# design.net
KiCad netlist of a schematic drawn in Altium Designer
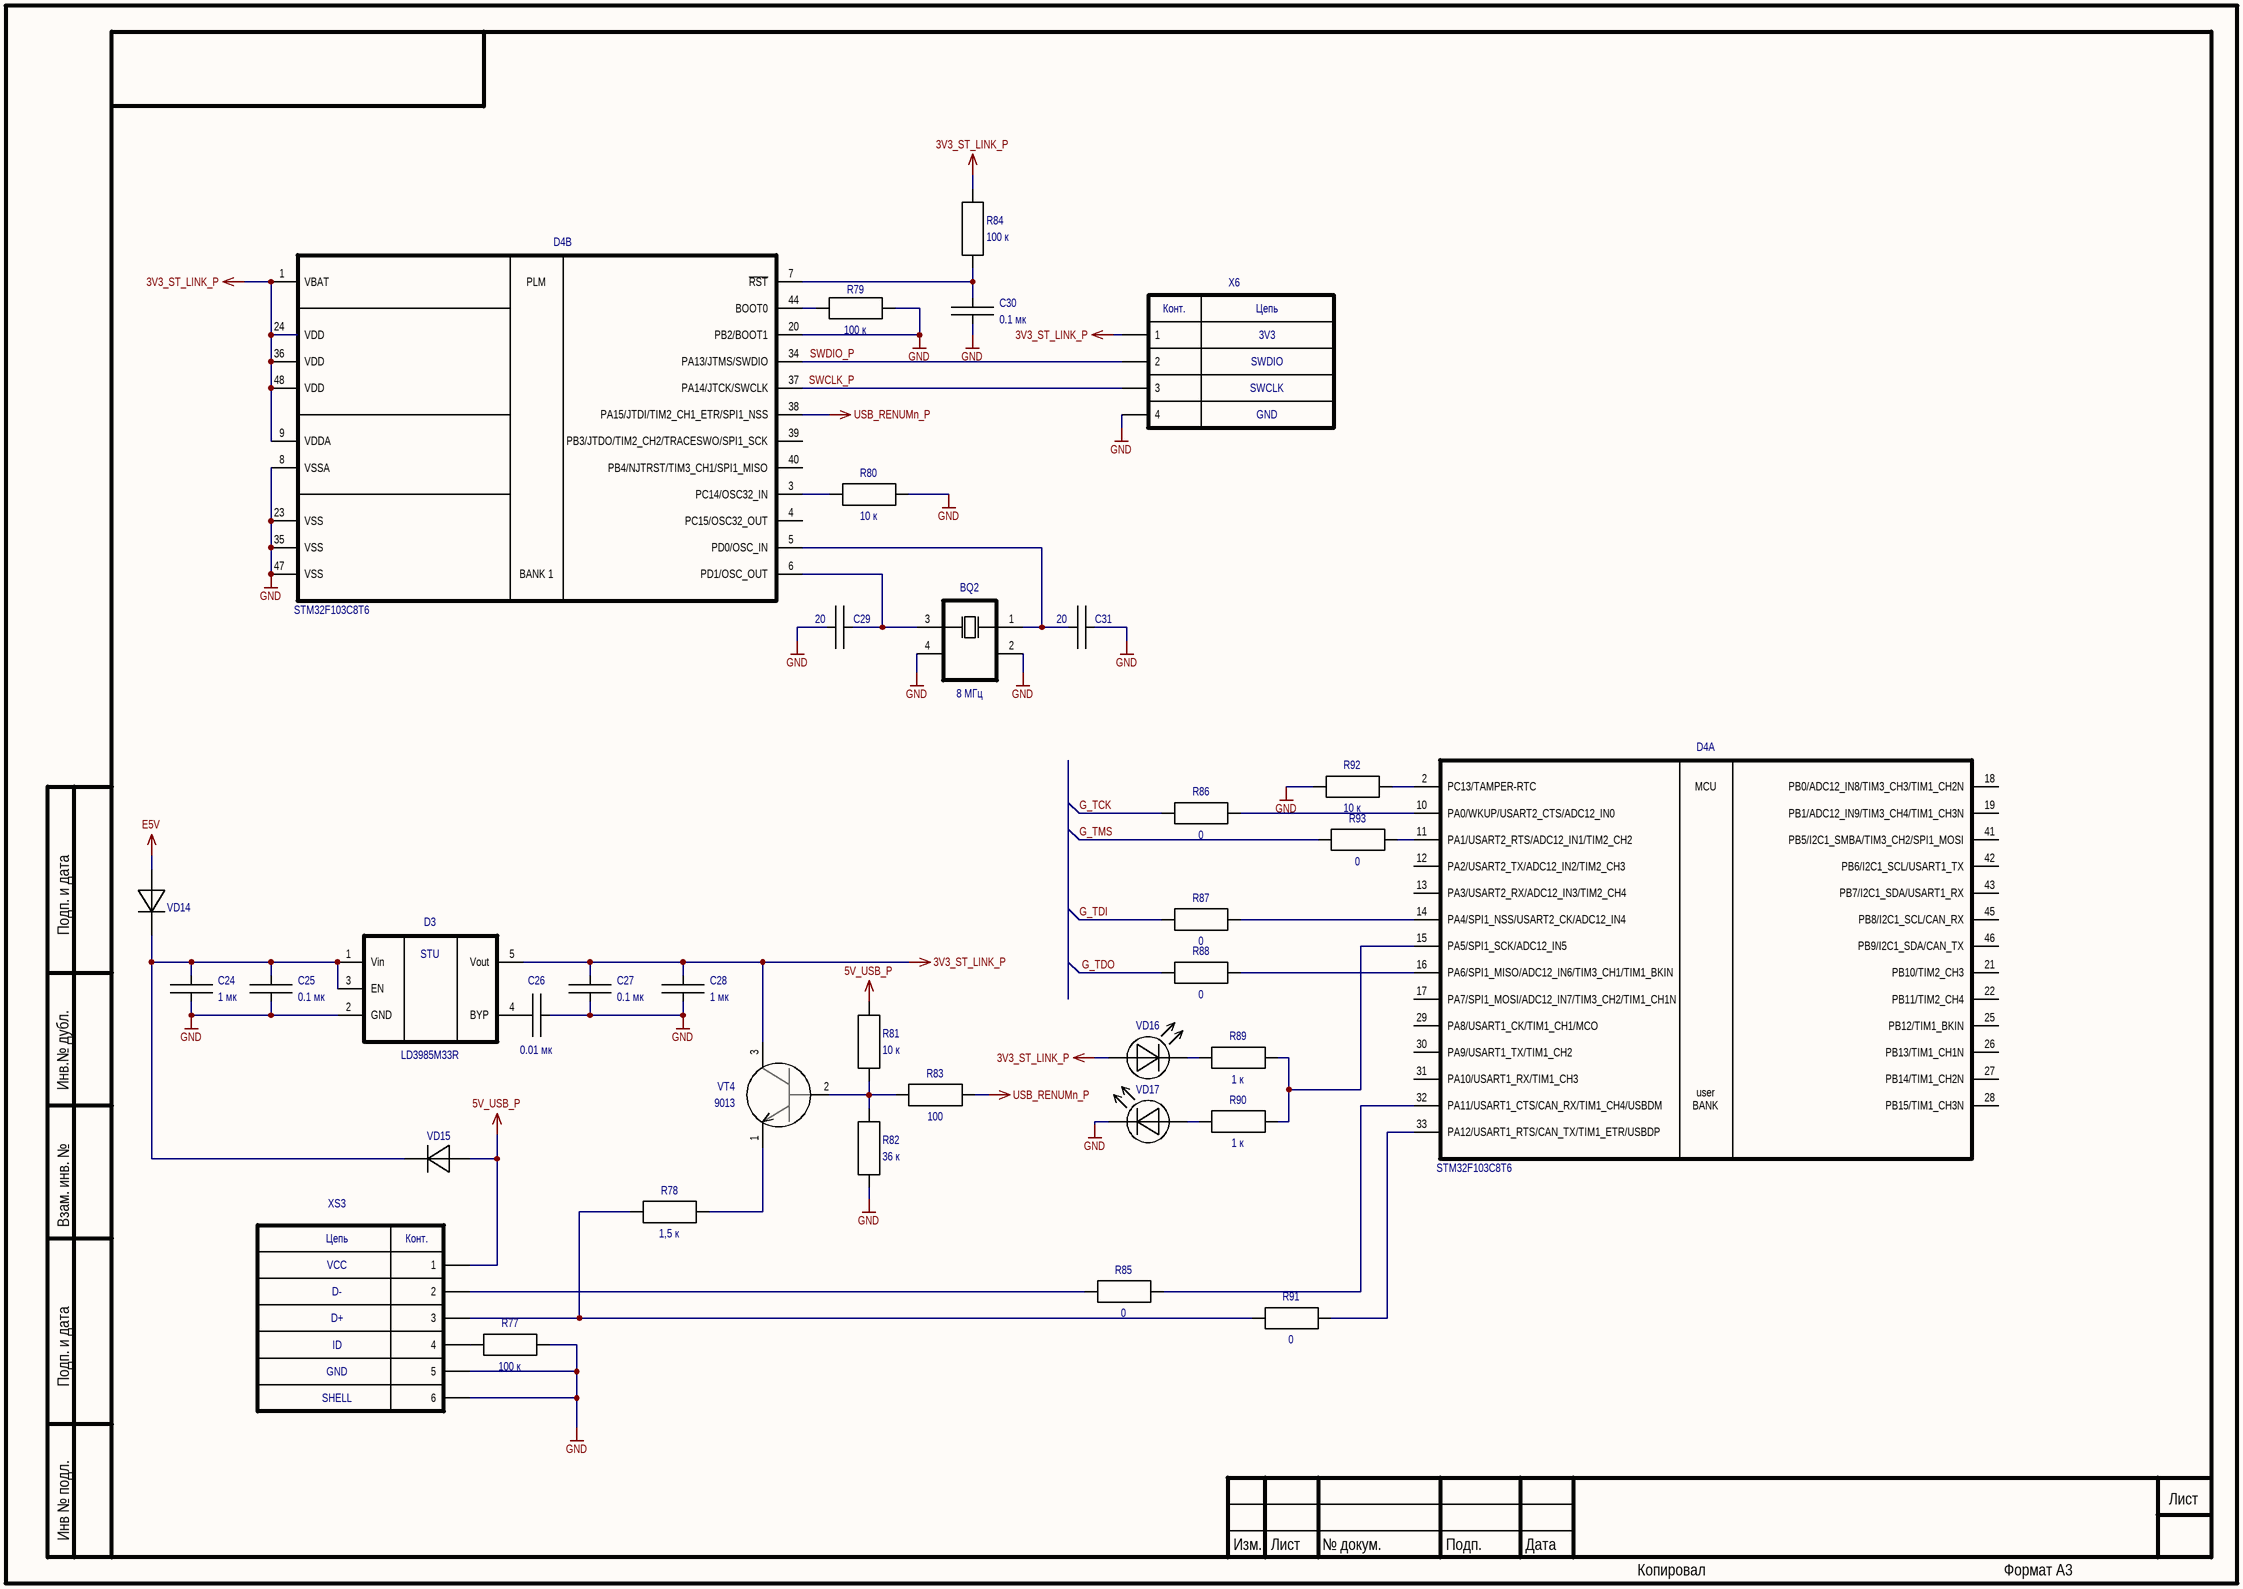
[diagram p0: программатор_ПЛИС.SchDoc]

(export (version "E")
  (design (tool "Eeschema 10.0.6"))
  (components
    (comp (ref "BQ2")
      (value "8 МГц")
      (footprint "SMD3225_4P20MHZ20PF10PPM")
      (fields (field (name "PARTNUMBER") "MQ-12.000-18") (field (name "Comment") "кварцевый резонатор_1"))
      (libsource (lib "Lisaveta_SCH") (part "кварцевый резонатор_1"))
    )
    (comp (ref "C24")
      (value "1 мк")
      (fields (field (name "Comment") "1 мкФ ±* * * *, *"))
      (libsource (lib "Lisaveta") (part "C"))
    )
    (comp (ref "C25")
      (value "0.1 мк")
      (fields (field (name "Comment") "0.1 мкФ ±* * * *, *"))
      (libsource (lib "Lisaveta") (part "C"))
    )
    (comp (ref "C26")
      (value "0.01 мк")
      (footprint "K10-79_1.6_0.8(0603)")
      (fields (field (name "Comment") "0.01 мкФ ±* * * *, *"))
      (libsource (lib "Lisaveta") (part "C"))
    )
    (comp (ref "C27")
      (value "0.1 мк")
      (fields (field (name "Comment") "0.1 мкФ ±* * * *, *"))
      (libsource (lib "Lisaveta") (part "C"))
    )
    (comp (ref "C28")
      (value "1 мк")
      (fields (field (name "Comment") "1 мкФ ±* * * *, *"))
      (libsource (lib "Lisaveta") (part "C"))
    )
    (comp (ref "C29")
      (value "20")
      (fields (field (name "Comment") "20Ф ±* * * *, *"))
      (libsource (lib "Lisaveta") (part "C"))
    )
    (comp (ref "C30")
      (value "0.1 мк")
      (fields (field (name "Comment") "0.1 мкФ ±* * * *, *"))
      (libsource (lib "Lisaveta") (part "C"))
    )
    (comp (ref "C31")
      (value "20")
      (fields (field (name "Comment") "20Ф ±* * * *, *"))
      (libsource (lib "Lisaveta") (part "C"))
    )
    (comp (ref "D3")
      (value "LD3985M33R")
      (footprint "SOT-23-5")
      (fields
        (field (name "PARTNUMBER") "LT1761ES5-2.5")
        (field (name "Comment") "LT1761ES5-2.5 (TSOT-23) Linear Technology")
      )
      (libsource (lib "Lisaveta") (part "LD3985M33R"))
    )
    (comp (ref "D4")
      (value "STM32F103C8T6")
      (footprint "LQFP48")
      (fields (field (name "Comment") " (LQFP-48) Xilinx"))
      (libsource (lib "Lisaveta") (part "stm32f103c8t6"))
    )
    (comp (ref "R77")
      (value "100 к")
      (fields (field (name "Comment") "100 кОм ±* *, *"))
      (libsource (lib "Lisaveta") (part "R"))
    )
    (comp (ref "R78")
      (value "1,5 к")
      (fields (field (name "Comment") "1,5 кОм ±* *, *"))
      (libsource (lib "Lisaveta") (part "R"))
    )
    (comp (ref "R79")
      (value "100 к")
      (fields (field (name "Comment") "100 кОм ±* *, *"))
      (libsource (lib "Lisaveta") (part "R"))
    )
    (comp (ref "R80")
      (value "10 к")
      (fields (field (name "Comment") "10 кОм ±* *, *"))
      (libsource (lib "Lisaveta") (part "R"))
    )
    (comp (ref "R81")
      (value "10 к")
      (fields (field (name "Comment") "10 кОм ±* *, *"))
      (libsource (lib "Lisaveta") (part "R_1"))
    )
    (comp (ref "R82")
      (value "36 к")
      (fields (field (name "Comment") "36 кОм ±* *, *"))
      (libsource (lib "Lisaveta") (part "R_1"))
    )
    (comp (ref "R83")
      (value "100")
      (fields (field (name "Comment") "100Ом ±* *, *"))
      (libsource (lib "Lisaveta") (part "R"))
    )
    (comp (ref "R84")
      (value "100 к")
      (footprint "RES 0603")
      (fields (field (name "Comment") "100 кОм ±* *, *"))
      (libsource (lib "Lisaveta") (part "R_1"))
    )
    (comp (ref "R85")
      (value "0")
      (fields (field (name "Comment") "0Ом ±* *, *"))
      (libsource (lib "Lisaveta") (part "R"))
    )
    (comp (ref "R86")
      (value "0")
      (fields (field (name "Comment") "0Ом ±* *, *"))
      (libsource (lib "Lisaveta") (part "R"))
    )
    (comp (ref "R87")
      (value "0")
      (fields (field (name "Comment") "0Ом ±* *, *"))
      (libsource (lib "Lisaveta") (part "R"))
    )
    (comp (ref "R88")
      (value "0")
      (fields (field (name "Comment") "0Ом ±* *, *"))
      (libsource (lib "Lisaveta") (part "R"))
    )
    (comp (ref "R89")
      (value "1 к")
      (fields (field (name "Comment") "1 кОм ±* *, *"))
      (libsource (lib "Lisaveta") (part "R"))
    )
    (comp (ref "R90")
      (value "1 к")
      (fields (field (name "Comment") "1 кОм ±* *, *"))
      (libsource (lib "Lisaveta") (part "R"))
    )
    (comp (ref "R91")
      (value "0")
      (fields (field (name "Comment") "0Ом ±* *, *"))
      (libsource (lib "") (part "R_1"))
    )
    (comp (ref "R92")
      (value "10 к")
      (fields (field (name "Comment") "10 кОм ±* *, *"))
      (libsource (lib "Lisaveta") (part "R"))
    )
    (comp (ref "R93")
      (value "0")
      (fields (field (name "Comment") "0Ом ±* *, *"))
      (libsource (lib "Lisaveta") (part "R"))
    )
    (comp (ref "VD14") (value "BAS316") (footprint "SOD323") (libsource (lib "Lisaveta") (part "BAS316")))
    (comp (ref "VD15") (value "BAS316") (footprint "SOD-323") (libsource (lib "Lisaveta") (part "BAS316")))
    (comp (ref "VD16")
      (value "Светодиод")
      (footprint "LED 0603")
      (libsource (lib "Lisaveta") (part "Светодиод"))
    )
    (comp (ref "VD17")
      (value "Светодиод")
      (footprint "LED 0603")
      (libsource (lib "Lisaveta") (part "Светодиод"))
    )
    (comp (ref "VT4")
      (value "9013")
      (footprint "SOT23(KT-46)")
      (fields (field (name "PARTNUMBER") "BC847C") (field (name "Comment") "BC847C (SOT-23) NXP"))
      (libsource (lib "Lisaveta") (part "T!9013"))
    )
    (comp (ref "X6")
      (value "KONT_POLE_4")
      (fields
        (field (name "1") "3V3")
        (field (name "2") "SWDIO")
        (field (name "3") "SWCLK")
        (field (name "4") "GND")
      )
      (libsource (lib "Lisaveta") (part "KONT_POLE_4"))
    )
    (comp (ref "XS3")
      (value "KONT_POLE_USB_DBG")
      (footprint "micro_USB")
      (fields
        (field (name "1") "VCC")
        (field (name "3") "D+")
        (field (name "2") "D-")
        (field (name "4") "ID")
        (field (name "6") "SHELL")
        (field (name "5") "GND")
      )
      (libsource (lib "Lisaveta") (part "KONT_POLE_USB_DBG"))
    )
  )
  (nets
    (net (code "1") (name "/G_TCK") (class "Default")
      (node (ref "R86") (pin "1") (pinfunction "1_1") (pintype "passive"))
    )
    (net (code "2") (name "/G_TDI") (class "Default")
      (node (ref "R87") (pin "1") (pinfunction "1_1") (pintype "passive"))
    )
    (net (code "3") (name "/G_TDO") (class "Default")
      (node (ref "R88") (pin "1") (pinfunction "1_1") (pintype "passive"))
    )
    (net (code "4") (name "/G_TMS") (class "Default")
      (node (ref "R93") (pin "1") (pinfunction "1_1") (pintype "passive"))
    )
    (net (code "5") (name "/SWCLK_P") (class "Default")
      (node (ref "D4") (pin "37") (pinfunction "PA14/JTCK/SWCLK_37") (pintype "passive"))
      (node (ref "X6") (pin "3") (pinfunction "3_3") (pintype "passive"))
    )
    (net (code "6") (name "/SWDIO_P") (class "Default")
      (node (ref "D4") (pin "34") (pinfunction "PA13/JTMS/SWDIO_34") (pintype "passive"))
      (node (ref "X6") (pin "2") (pinfunction "2_2") (pintype "passive"))
    )
    (net (code "7") (name "3V3_ST_LINK_P") (class "Default")
      (node (ref "C27") (pin "2") (pinfunction "2_2") (pintype "passive"))
      (node (ref "C28") (pin "2") (pinfunction "2_2") (pintype "passive"))
      (node (ref "D3") (pin "5") (pinfunction "Vout_5") (pintype "passive"))
      (node (ref "D4") (pin "1") (pinfunction "VBAT_1") (pintype "passive"))
      (node (ref "D4") (pin "24") (pinfunction "VDD_24") (pintype "passive"))
      (node (ref "D4") (pin "36") (pinfunction "VDD_36") (pintype "passive"))
      (node (ref "D4") (pin "48") (pinfunction "VDD_48") (pintype "passive"))
      (node (ref "D4") (pin "9") (pinfunction "VDDA_9") (pintype "passive"))
      (node (ref "R84") (pin "1") (pinfunction "1_1") (pintype "passive"))
      (node (ref "VD16") (pin "1") (pinfunction "A_1") (pintype "passive"))
      (node (ref "VT4") (pin "3") (pinfunction "3_3") (pintype "passive"))
      (node (ref "X6") (pin "1") (pinfunction "1_1") (pintype "passive"))
    )
    (net (code "8") (name "5V_USB_P") (class "Default")
      (node (ref "R81") (pin "1") (pinfunction "1_1") (pintype "passive"))
      (node (ref "VD15") (pin "1") (pinfunction "1_1") (pintype "passive"))
      (node (ref "XS3") (pin "1") (pinfunction "1_1") (pintype "passive"))
    )
    (net (code "9") (name "E5V") (class "Default")
      (node (ref "VD14") (pin "1") (pinfunction "1_1") (pintype "passive"))
    )
    (net (code "10") (name "GND") (class "Default")
      (node (ref "BQ2") (pin "2") (pinfunction "GND_2") (pintype "passive"))
      (node (ref "BQ2") (pin "4") (pinfunction "GND_4") (pintype "passive"))
      (node (ref "C24") (pin "1") (pinfunction "1_1") (pintype "passive"))
      (node (ref "C25") (pin "1") (pinfunction "1_1") (pintype "passive"))
      (node (ref "C26") (pin "1") (pinfunction "1_1") (pintype "passive"))
      (node (ref "C27") (pin "1") (pinfunction "1_1") (pintype "passive"))
      (node (ref "C28") (pin "1") (pinfunction "1_1") (pintype "passive"))
      (node (ref "C29") (pin "2") (pinfunction "2_2") (pintype "passive"))
      (node (ref "C30") (pin "2") (pinfunction "2_2") (pintype "passive"))
      (node (ref "C31") (pin "1") (pinfunction "1_1") (pintype "passive"))
      (node (ref "D3") (pin "2") (pinfunction "GND_2") (pintype "passive"))
      (node (ref "D4") (pin "20") (pinfunction "PB2/BOOT1_20") (pintype "passive"))
      (node (ref "D4") (pin "23") (pinfunction "VSS_23") (pintype "passive"))
      (node (ref "D4") (pin "35") (pinfunction "VSS_35") (pintype "passive"))
      (node (ref "D4") (pin "47") (pinfunction "VSS_47") (pintype "passive"))
      (node (ref "D4") (pin "8") (pinfunction "VSSA_8") (pintype "passive"))
      (node (ref "R77") (pin "2") (pinfunction "2_2") (pintype "passive"))
      (node (ref "R79") (pin "2") (pinfunction "2_2") (pintype "passive"))
      (node (ref "R80") (pin "1") (pinfunction "1_1") (pintype "passive"))
      (node (ref "R82") (pin "2") (pinfunction "2_2") (pintype "passive"))
      (node (ref "R92") (pin "1") (pinfunction "1_1") (pintype "passive"))
      (node (ref "VD17") (pin "2") (pinfunction "C_2") (pintype "passive"))
      (node (ref "X6") (pin "4") (pinfunction "4_4") (pintype "passive"))
      (node (ref "XS3") (pin "5") (pinfunction "5_5") (pintype "passive"))
      (node (ref "XS3") (pin "6") (pinfunction "6_6") (pintype "passive"))
    )
    (net (code "11") (name "Net-(D3-BYP)") (class "Default")
      (node (ref "C26") (pin "2") (pinfunction "2_2") (pintype "passive"))
      (node (ref "D3") (pin "4") (pinfunction "BYP_4") (pintype "passive"))
    )
    (net (code "12") (name "Net-(D3-EN)") (class "Default")
      (node (ref "C24") (pin "2") (pinfunction "2_2") (pintype "passive"))
      (node (ref "C25") (pin "2") (pinfunction "2_2") (pintype "passive"))
      (node (ref "D3") (pin "1") (pinfunction "Vin_1") (pintype "passive"))
      (node (ref "D3") (pin "3") (pinfunction "EN_3") (pintype "passive"))
      (node (ref "VD14") (pin "2") (pinfunction "2_2") (pintype "passive"))
      (node (ref "VD15") (pin "2") (pinfunction "2_2") (pintype "passive"))
    )
    (net (code "13") (name "Net-(D4A-PA0{slash}WKUP{slash}USART2_CTS{slash}ADC12_IN0)") (class "Default")
      (node (ref "D4") (pin "10") (pinfunction "PA0/WKUP/USART2_CTS/ADC12_IN0_10") (pintype "passive"))
      (node (ref "R86") (pin "2") (pinfunction "2_2") (pintype "passive"))
    )
    (net (code "14") (name "Net-(D4A-PA1{slash}USART2_RTS{slash}ADC12_IN1{slash}TIM2_CH2)") (class "Default")
      (node (ref "D4") (pin "11") (pinfunction "PA1/USART2_RTS/ADC12_IN1/TIM2_CH2_11") (pintype "passive"))
      (node (ref "R93") (pin "2") (pinfunction "2_2") (pintype "passive"))
    )
    (net (code "15") (name "Net-(D4A-PA4{slash}SPI1_NSS{slash}USART2_CK{slash}ADC12_IN4)") (class "Default")
      (node (ref "D4") (pin "14") (pinfunction "PA4/SPI1_NSS/USART2_CK/ADC12_IN4_14") (pintype "passive"))
      (node (ref "R87") (pin "2") (pinfunction "2_2") (pintype "passive"))
    )
    (net (code "16") (name "Net-(D4A-PA5{slash}SPI1_SCK{slash}ADC12_IN5)") (class "Default")
      (node (ref "D4") (pin "15") (pinfunction "PA5/SPI1_SCK/ADC12_IN5_15") (pintype "passive"))
      (node (ref "R89") (pin "2") (pinfunction "2_2") (pintype "passive"))
      (node (ref "R90") (pin "2") (pinfunction "2_2") (pintype "passive"))
    )
    (net (code "17") (name "Net-(D4A-PA6{slash}SPI1_MISO{slash}ADC12_IN6{slash}TIM3_CH1{slash}TIM1_BKIN)") (class "Default")
      (node (ref "D4") (pin "16") (pinfunction "PA6/SPI1_MISO/ADC12_IN6/TIM3_CH1/TIM1_BKIN_16") (pintype "passive"))
      (node (ref "R88") (pin "2") (pinfunction "2_2") (pintype "passive"))
    )
    (net (code "18") (name "Net-(D4A-PA11{slash}USART1_CTS{slash}CAN_RX{slash}TIM1_CH4{slash}USBDM)") (class "Default")
      (node (ref "D4") (pin "32") (pinfunction "PA11/USART1_CTS/CAN_RX/TIM1_CH4/USBDM_32") (pintype "passive"))
      (node (ref "R85") (pin "2") (pinfunction "2_2") (pintype "passive"))
    )
    (net (code "19") (name "Net-(D4A-PA12{slash}USART1_RTS{slash}CAN_TX{slash}TIM1_ETR{slash}USBDP)") (class "Default")
      (node (ref "D4") (pin "33") (pinfunction "PA12/USART1_RTS/CAN_TX/TIM1_ETR/USBDP_33") (pintype "passive"))
      (node (ref "R91") (pin "2") (pinfunction "2_2") (pintype "passive"))
    )
    (net (code "20") (name "Net-(D4A-PC13{slash}TAMPER-RTC)") (class "Default")
      (node (ref "D4") (pin "2") (pinfunction "PC13/TAMPER-RTC_2") (pintype "passive"))
      (node (ref "R92") (pin "2") (pinfunction "2_2") (pintype "passive"))
    )
    (net (code "21") (name "Net-(D4B-BOOT0)") (class "Default")
      (node (ref "D4") (pin "44") (pinfunction "BOOT0_44") (pintype "passive"))
      (node (ref "R79") (pin "1") (pinfunction "1_1") (pintype "passive"))
    )
    (net (code "22") (name "Net-(D4B-PC14{slash}OSC32_IN)") (class "Default")
      (node (ref "D4") (pin "3") (pinfunction "PC14/OSC32_IN_3") (pintype "passive"))
      (node (ref "R80") (pin "2") (pinfunction "2_2") (pintype "passive"))
    )
    (net (code "23") (name "Net-(D4B-PD0{slash}OSC_IN)") (class "Default")
      (node (ref "BQ2") (pin "1") (pinfunction "1_1") (pintype "passive"))
      (node (ref "C31") (pin "2") (pinfunction "2_2") (pintype "passive"))
      (node (ref "D4") (pin "5") (pinfunction "PD0/OSC_IN_5") (pintype "passive"))
    )
    (net (code "24") (name "Net-(D4B-PD1{slash}OSC_OUT)") (class "Default")
      (node (ref "BQ2") (pin "3") (pinfunction "3_3") (pintype "passive"))
      (node (ref "C29") (pin "1") (pinfunction "1_1") (pintype "passive"))
      (node (ref "D4") (pin "6") (pinfunction "PD1/OSC_OUT_6") (pintype "passive"))
    )
    (net (code "25") (name "Net-(D4B-~{RST})") (class "Default")
      (node (ref "C30") (pin "1") (pinfunction "1_1") (pintype "passive"))
      (node (ref "D4") (pin "7") (pinfunction "~{RST}_7") (pintype "passive"))
      (node (ref "R84") (pin "2") (pinfunction "2_2") (pintype "passive"))
    )
    (net (code "26") (name "Net-(R77-Pad1)") (class "Default")
      (node (ref "R77") (pin "1") (pinfunction "1_1") (pintype "passive"))
      (node (ref "XS3") (pin "4") (pinfunction "4_4") (pintype "passive"))
    )
    (net (code "27") (name "Net-(R78-Pad1)") (class "Default")
      (node (ref "R78") (pin "1") (pinfunction "1_1") (pintype "passive"))
      (node (ref "R91") (pin "1") (pinfunction "1_1") (pintype "passive"))
      (node (ref "XS3") (pin "3") (pinfunction "3_3") (pintype "passive"))
    )
    (net (code "28") (name "Net-(R78-Pad2)") (class "Default")
      (node (ref "R78") (pin "2") (pinfunction "2_2") (pintype "passive"))
      (node (ref "VT4") (pin "1") (pinfunction "1_1") (pintype "passive"))
    )
    (net (code "29") (name "Net-(R81-Pad2)") (class "Default")
      (node (ref "R81") (pin "2") (pinfunction "2_2") (pintype "passive"))
      (node (ref "R82") (pin "1") (pinfunction "1_1") (pintype "passive"))
      (node (ref "R83") (pin "1") (pinfunction "1_1") (pintype "passive"))
      (node (ref "VT4") (pin "2") (pinfunction "2_2") (pintype "passive"))
    )
    (net (code "30") (name "Net-(R85-Pad1)") (class "Default")
      (node (ref "R85") (pin "1") (pinfunction "1_1") (pintype "passive"))
      (node (ref "XS3") (pin "2") (pinfunction "2_2") (pintype "passive"))
    )
    (net (code "31") (name "Net-(VD16-C)") (class "Default")
      (node (ref "R89") (pin "1") (pinfunction "1_1") (pintype "passive"))
      (node (ref "VD16") (pin "2") (pinfunction "C_2") (pintype "passive"))
    )
    (net (code "32") (name "Net-(VD17-A)") (class "Default")
      (node (ref "R90") (pin "1") (pinfunction "1_1") (pintype "passive"))
      (node (ref "VD17") (pin "1") (pinfunction "A_1") (pintype "passive"))
    )
    (net (code "33") (name "USB_RENUMn_P") (class "Default")
      (node (ref "D4") (pin "38") (pinfunction "PA15/JTDI/TIM2_CH1_ETR/SPI1_NSS_38") (pintype "passive"))
      (node (ref "R83") (pin "2") (pinfunction "2_2") (pintype "passive"))
    )
    (net (code "34") (name "unconnected-(D4A-PA2{slash}USART2_TX{slash}ADC12_IN2{slash}TIM2_CH3-Pad12)") (class "Default")
      (node (ref "D4") (pin "12") (pinfunction "PA2/USART2_TX/ADC12_IN2/TIM2_CH3_12") (pintype "passive"))
    )
    (net (code "35") (name "unconnected-(D4A-PA3{slash}USART2_RX{slash}ADC12_IN3{slash}TIM2_CH4-Pad13)") (class "Default")
      (node (ref "D4") (pin "13") (pinfunction "PA3/USART2_RX/ADC12_IN3/TIM2_CH4_13") (pintype "passive"))
    )
    (net (code "36") (name "unconnected-(D4A-PA7{slash}SPI1_MOSI{slash}ADC12_IN7{slash}TIM3_CH2{slash}TIM1_CH1N-Pad17)") (class "Default")
      (node (ref "D4") (pin "17") (pinfunction "PA7/SPI1_MOSI/ADC12_IN7/TIM3_CH2/TIM1_CH1N_17") (pintype "passive"))
    )
    (net (code "37") (name "unconnected-(D4A-PA8{slash}USART1_CK{slash}TIM1_CH1{slash}MCO-Pad29)") (class "Default")
      (node (ref "D4") (pin "29") (pinfunction "PA8/USART1_CK/TIM1_CH1/MCO_29") (pintype "passive"))
    )
    (net (code "38") (name "unconnected-(D4A-PA9{slash}USART1_TX{slash}TIM1_CH2-Pad30)") (class "Default")
      (node (ref "D4") (pin "30") (pinfunction "PA9/USART1_TX/TIM1_CH2_30") (pintype "passive"))
    )
    (net (code "39") (name "unconnected-(D4A-PA10{slash}USART1_RX{slash}TIM1_CH3-Pad31)") (class "Default")
      (node (ref "D4") (pin "31") (pinfunction "PA10/USART1_RX/TIM1_CH3_31") (pintype "passive"))
    )
    (net (code "40") (name "unconnected-(D4A-PB0{slash}ADC12_IN8{slash}TIM3_CH3{slash}TIM1_CH2N-Pad18)") (class "Default")
      (node (ref "D4") (pin "18") (pinfunction "PB0/ADC12_IN8/TIM3_CH3/TIM1_CH2N_18") (pintype "passive"))
    )
    (net (code "41") (name "unconnected-(D4A-PB1{slash}ADC12_IN9{slash}TIM3_CH4{slash}TIM1_CH3N-Pad19)") (class "Default")
      (node (ref "D4") (pin "19") (pinfunction "PB1/ADC12_IN9/TIM3_CH4/TIM1_CH3N_19") (pintype "passive"))
    )
    (net (code "42") (name "unconnected-(D4A-PB5{slash}I2C1_SMBA{slash}TIM3_CH2{slash}SPI1_MOSI-Pad41)") (class "Default")
      (node (ref "D4") (pin "41") (pinfunction "PB5/I2C1_SMBA/TIM3_CH2/SPI1_MOSI_41") (pintype "passive"))
    )
    (net (code "43") (name "unconnected-(D4A-PB6{slash}I2C1_SCL{slash}USART1_TX-Pad42)") (class "Default")
      (node (ref "D4") (pin "42") (pinfunction "PB6/I2C1_SCL/USART1_TX_42") (pintype "passive"))
    )
    (net (code "44") (name "unconnected-(D4A-PB7{slash}I2C1_SDA{slash}USART1_RX-Pad43)") (class "Default")
      (node (ref "D4") (pin "43") (pinfunction "PB7/I2C1_SDA/USART1_RX_43") (pintype "passive"))
    )
    (net (code "45") (name "unconnected-(D4A-PB8{slash}I2C1_SCL{slash}CAN_RX-Pad45)") (class "Default")
      (node (ref "D4") (pin "45") (pinfunction "PB8/I2C1_SCL/CAN_RX_45") (pintype "passive"))
    )
    (net (code "46") (name "unconnected-(D4A-PB9{slash}I2C1_SDA{slash}CAN_TX-Pad46)") (class "Default")
      (node (ref "D4") (pin "46") (pinfunction "PB9/I2C1_SDA/CAN_TX_46") (pintype "passive"))
    )
    (net (code "47") (name "unconnected-(D4A-PB10{slash}TIM2_CH3-Pad21)") (class "Default")
      (node (ref "D4") (pin "21") (pinfunction "PB10/TIM2_CH3_21") (pintype "passive"))
    )
    (net (code "48") (name "unconnected-(D4A-PB11{slash}TIM2_CH4-Pad22)") (class "Default")
      (node (ref "D4") (pin "22") (pinfunction "PB11/TIM2_CH4_22") (pintype "passive"))
    )
    (net (code "49") (name "unconnected-(D4A-PB12{slash}TIM1_BKIN-Pad25)") (class "Default")
      (node (ref "D4") (pin "25") (pinfunction "PB12/TIM1_BKIN_25") (pintype "passive"))
    )
    (net (code "50") (name "unconnected-(D4A-PB13{slash}TIM1_CH1N-Pad26)") (class "Default")
      (node (ref "D4") (pin "26") (pinfunction "PB13/TIM1_CH1N_26") (pintype "passive"))
    )
    (net (code "51") (name "unconnected-(D4A-PB14{slash}TIM1_CH2N-Pad27)") (class "Default")
      (node (ref "D4") (pin "27") (pinfunction "PB14/TIM1_CH2N_27") (pintype "passive"))
    )
    (net (code "52") (name "unconnected-(D4A-PB15{slash}TIM1_CH3N-Pad28)") (class "Default")
      (node (ref "D4") (pin "28") (pinfunction "PB15/TIM1_CH3N_28") (pintype "passive"))
    )
    (net (code "53") (name "unconnected-(D4B-PB3{slash}JTDO{slash}TIM2_CH2{slash}TRACESWO{slash}SPI1_SCK-Pad39)") (class "Default")
      (node (ref "D4") (pin "39") (pinfunction "PB3/JTDO/TIM2_CH2/TRACESWO/SPI1_SCK_39") (pintype "passive"))
    )
    (net (code "54") (name "unconnected-(D4B-PB4{slash}NJTRST{slash}TIM3_CH1{slash}SPI1_MISO-Pad40)") (class "Default")
      (node (ref "D4") (pin "40") (pinfunction "PB4/NJTRST/TIM3_CH1/SPI1_MISO_40") (pintype "passive"))
    )
    (net (code "55") (name "unconnected-(D4B-PC15{slash}OSC32_OUT-Pad4)") (class "Default")
      (node (ref "D4") (pin "4") (pinfunction "PC15/OSC32_OUT_4") (pintype "passive"))
    )
  )
)
